# Statemachine_ST7735_R03.net
KiCad netlist of a schematic drawn in EAGLE
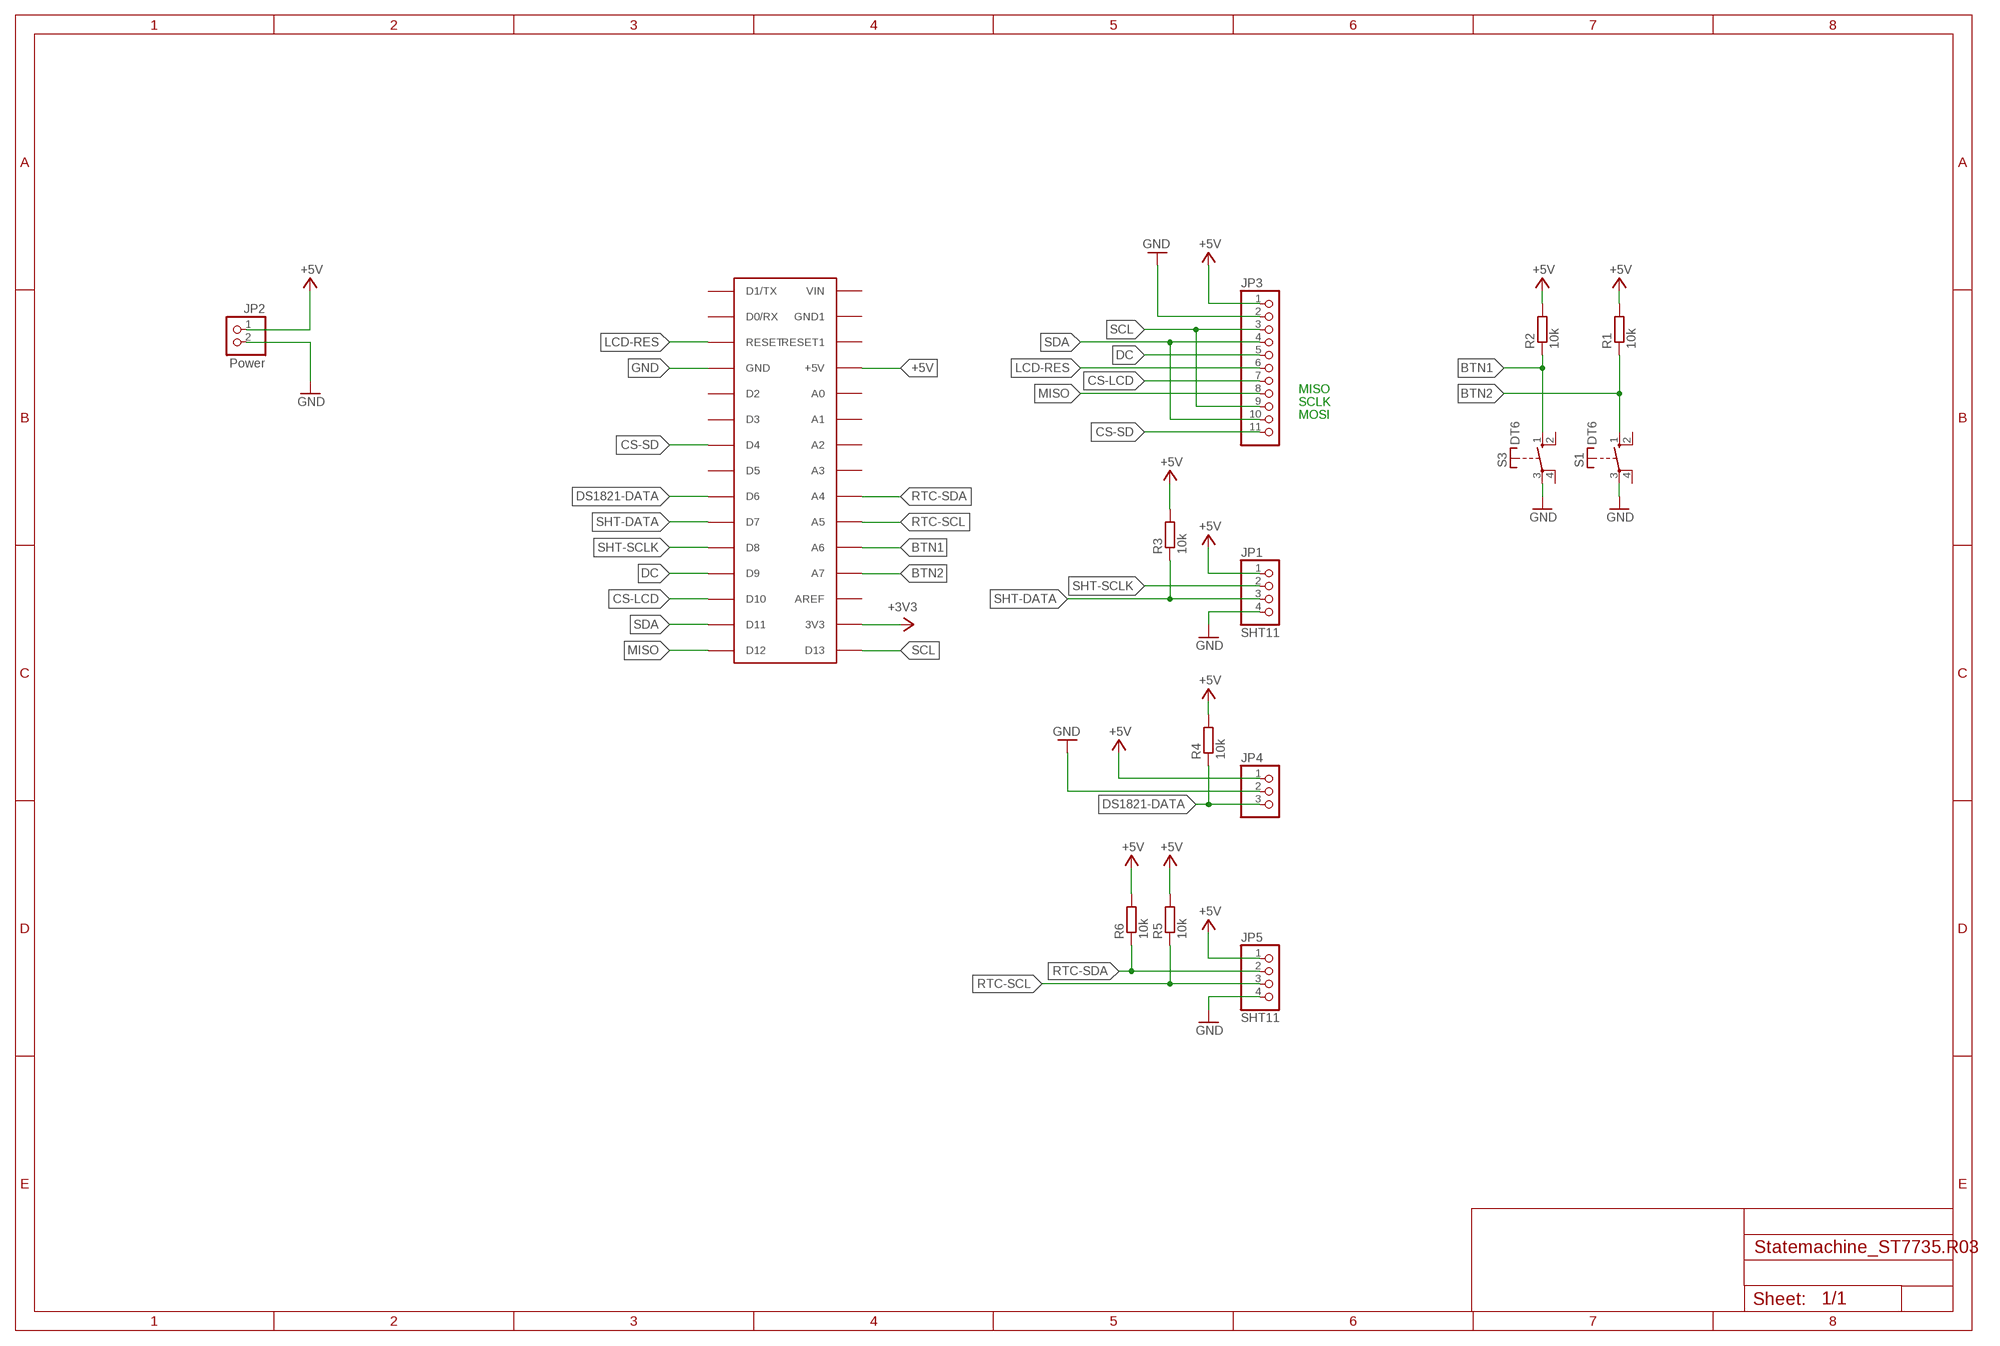
[diagram p0: schematic, sheet 1]

(export (version "E")
  (design (tool "Eeschema 10.0.6"))
  (components
    (comp (ref "JP1")
      (value "SHT11")
      (footprint "eagle-import:1X04")
      (libsource (lib "eagle-import") (part "PINHD-1X4"))
    )
    (comp (ref "JP2")
      (value "Power")
      (footprint "eagle-import:1X02")
      (libsource (lib "eagle-import") (part "PINHD-1X2"))
    )
    (comp (ref "JP3")
      (value "PINHD-1X11")
      (footprint "eagle-import:1X11")
      (libsource (lib "eagle-import") (part "PINHD-1X11"))
    )
    (comp (ref "JP4")
      (value "PINHD-1X3")
      (footprint "eagle-import:1X03")
      (libsource (lib "eagle-import") (part "PINHD-1X3"))
    )
    (comp (ref "JP5")
      (value "SHT11")
      (footprint "eagle-import:1X04")
      (libsource (lib "eagle-import") (part "PINHD-1X4"))
    )
    (comp (ref "NANO")
      (value "ARDUINONANO")
      (footprint "eagle-import:PDIP-32")
      (libsource (lib "eagle-import") (part "ARDUINONANO"))
    )
    (comp (ref "R1")
      (value "10k")
      (footprint "eagle-import:0204_7")
      (libsource (lib "eagle-import") (part "R-EU_0204/7"))
    )
    (comp (ref "R2")
      (value "10k")
      (footprint "eagle-import:0204_7")
      (libsource (lib "eagle-import") (part "R-EU_0204/7"))
    )
    (comp (ref "R3")
      (value "10k")
      (footprint "eagle-import:0204_7")
      (libsource (lib "eagle-import") (part "R-EU_0204/7"))
    )
    (comp (ref "R4")
      (value "10k")
      (footprint "eagle-import:0204_7")
      (libsource (lib "eagle-import") (part "R-EU_0204/7"))
    )
    (comp (ref "R5")
      (value "10k")
      (footprint "eagle-import:0204_7")
      (libsource (lib "eagle-import") (part "R-EU_0204/7"))
    )
    (comp (ref "R6")
      (value "10k")
      (footprint "eagle-import:0204_7")
      (libsource (lib "eagle-import") (part "R-EU_0204/7"))
    )
    (comp (ref "S1")
      (value "DT6")
      (footprint "eagle-import:DT6")
      (libsource (lib "eagle-import") (part "DT6"))
    )
    (comp (ref "S3")
      (value "DT6")
      (footprint "eagle-import:DT6")
      (libsource (lib "eagle-import") (part "DT6"))
    )
  )
  (nets
    (net (code "1") (name "+3V3") (class "Default")
      (node (ref "NANO") (pin "3V3") (pinfunction "3V3_3V3") (pintype "bidirectional"))
    )
    (net (code "2") (name "+5V") (class "Default")
      (node (ref "JP1") (pin "1") (pinfunction "1_1") (pintype "passive"))
      (node (ref "JP2") (pin "1") (pinfunction "1_1") (pintype "passive"))
      (node (ref "JP3") (pin "1") (pinfunction "1_1") (pintype "passive"))
      (node (ref "JP4") (pin "1") (pinfunction "1_1") (pintype "passive"))
      (node (ref "JP5") (pin "1") (pinfunction "1_1") (pintype "passive"))
      (node (ref "NANO") (pin "+5V") (pinfunction "+5V_+5V") (pintype "bidirectional"))
      (node (ref "R1") (pin "2") (pinfunction "2_2") (pintype "passive"))
      (node (ref "R2") (pin "2") (pinfunction "2_2") (pintype "passive"))
      (node (ref "R3") (pin "2") (pinfunction "2_2") (pintype "passive"))
      (node (ref "R4") (pin "2") (pinfunction "2_2") (pintype "passive"))
      (node (ref "R5") (pin "2") (pinfunction "2_2") (pintype "passive"))
      (node (ref "R6") (pin "2") (pinfunction "2_2") (pintype "passive"))
    )
    (net (code "3") (name "BTN1") (class "Default")
      (node (ref "NANO") (pin "A6") (pinfunction "A6_A6") (pintype "bidirectional"))
      (node (ref "R2") (pin "1") (pinfunction "1_1") (pintype "passive"))
      (node (ref "S3") (pin "1") (pinfunction "S_1") (pintype "passive"))
    )
    (net (code "4") (name "BTN2") (class "Default")
      (node (ref "NANO") (pin "A7") (pinfunction "A7_A7") (pintype "bidirectional"))
      (node (ref "R1") (pin "1") (pinfunction "1_1") (pintype "passive"))
      (node (ref "S1") (pin "1") (pinfunction "S_1") (pintype "passive"))
    )
    (net (code "5") (name "CS-LCD") (class "Default")
      (node (ref "JP3") (pin "7") (pinfunction "7_7") (pintype "passive"))
      (node (ref "NANO") (pin "D10") (pinfunction "D10_D10") (pintype "bidirectional"))
    )
    (net (code "6") (name "CS-SD") (class "Default")
      (node (ref "JP3") (pin "11") (pinfunction "11_11") (pintype "passive"))
      (node (ref "NANO") (pin "D4") (pinfunction "D4_D4") (pintype "bidirectional"))
    )
    (net (code "7") (name "DC") (class "Default")
      (node (ref "JP3") (pin "5") (pinfunction "5_5") (pintype "passive"))
      (node (ref "NANO") (pin "D9") (pinfunction "D9_D9") (pintype "bidirectional"))
    )
    (net (code "8") (name "DS1821-DATA") (class "Default")
      (node (ref "JP4") (pin "3") (pinfunction "3_3") (pintype "passive"))
      (node (ref "NANO") (pin "D6") (pinfunction "D6_D6") (pintype "bidirectional"))
      (node (ref "R4") (pin "1") (pinfunction "1_1") (pintype "passive"))
    )
    (net (code "9") (name "GND") (class "Default")
      (node (ref "JP1") (pin "4") (pinfunction "4_4") (pintype "passive"))
      (node (ref "JP2") (pin "2") (pinfunction "2_2") (pintype "passive"))
      (node (ref "JP3") (pin "2") (pinfunction "2_2") (pintype "passive"))
      (node (ref "JP4") (pin "2") (pinfunction "2_2") (pintype "passive"))
      (node (ref "JP5") (pin "4") (pinfunction "4_4") (pintype "passive"))
      (node (ref "NANO") (pin "GND") (pinfunction "GND_GND") (pintype "bidirectional"))
      (node (ref "S1") (pin "3") (pinfunction "P_3") (pintype "passive"))
      (node (ref "S3") (pin "3") (pinfunction "P_3") (pintype "passive"))
    )
    (net (code "10") (name "LCD-RES") (class "Default")
      (node (ref "JP3") (pin "6") (pinfunction "6_6") (pintype "passive"))
      (node (ref "NANO") (pin "RESET") (pinfunction "RESET_RESET") (pintype "bidirectional"))
    )
    (net (code "11") (name "MISO") (class "Default")
      (node (ref "JP3") (pin "8") (pinfunction "8_8") (pintype "passive"))
      (node (ref "NANO") (pin "D12") (pinfunction "D12_D12") (pintype "bidirectional"))
    )
    (net (code "12") (name "RTC-SCL") (class "Default")
      (node (ref "JP5") (pin "3") (pinfunction "3_3") (pintype "passive"))
      (node (ref "NANO") (pin "A5") (pinfunction "A5_A5") (pintype "bidirectional"))
      (node (ref "R5") (pin "1") (pinfunction "1_1") (pintype "passive"))
    )
    (net (code "13") (name "RTC-SDA") (class "Default")
      (node (ref "JP5") (pin "2") (pinfunction "2_2") (pintype "passive"))
      (node (ref "NANO") (pin "A4") (pinfunction "A4_A4") (pintype "bidirectional"))
      (node (ref "R6") (pin "1") (pinfunction "1_1") (pintype "passive"))
    )
    (net (code "14") (name "SCL") (class "Default")
      (node (ref "JP3") (pin "3") (pinfunction "3_3") (pintype "passive"))
      (node (ref "JP3") (pin "9") (pinfunction "9_9") (pintype "passive"))
      (node (ref "NANO") (pin "D13") (pinfunction "D13_D13") (pintype "bidirectional"))
    )
    (net (code "15") (name "SDA") (class "Default")
      (node (ref "JP3") (pin "10") (pinfunction "10_10") (pintype "passive"))
      (node (ref "JP3") (pin "4") (pinfunction "4_4") (pintype "passive"))
      (node (ref "NANO") (pin "D11") (pinfunction "D11_D11") (pintype "bidirectional"))
    )
    (net (code "16") (name "SHT-DATA") (class "Default")
      (node (ref "JP1") (pin "3") (pinfunction "3_3") (pintype "passive"))
      (node (ref "NANO") (pin "D7") (pinfunction "D7_D7") (pintype "bidirectional"))
      (node (ref "R3") (pin "1") (pinfunction "1_1") (pintype "passive"))
    )
    (net (code "17") (name "SHT-SCLK") (class "Default")
      (node (ref "JP1") (pin "2") (pinfunction "2_2") (pintype "passive"))
      (node (ref "NANO") (pin "D8") (pinfunction "D8_D8") (pintype "bidirectional"))
    )
    (net (code "18") (name "unconnected-(NANO-PadA0)") (class "Default")
      (node (ref "NANO") (pin "A0") (pinfunction "A0_A0") (pintype "bidirectional"))
    )
    (net (code "19") (name "unconnected-(NANO-PadA1)") (class "Default")
      (node (ref "NANO") (pin "A1") (pinfunction "A1_A1") (pintype "bidirectional"))
    )
    (net (code "20") (name "unconnected-(NANO-PadA2)") (class "Default")
      (node (ref "NANO") (pin "A2") (pinfunction "A2_A2") (pintype "bidirectional"))
    )
    (net (code "21") (name "unconnected-(NANO-PadA3)") (class "Default")
      (node (ref "NANO") (pin "A3") (pinfunction "A3_A3") (pintype "bidirectional"))
    )
    (net (code "22") (name "unconnected-(NANO-PadAREF)") (class "Default")
      (node (ref "NANO") (pin "AREF") (pinfunction "AREF_AREF") (pintype "bidirectional"))
    )
    (net (code "23") (name "unconnected-(NANO-PadD0{slash}RX)") (class "Default")
      (node (ref "NANO") (pin "D0/RX") (pinfunction "D0/RX_D0/RX") (pintype "bidirectional"))
    )
    (net (code "24") (name "unconnected-(NANO-PadD1{slash}TX)") (class "Default")
      (node (ref "NANO") (pin "D1/TX") (pinfunction "D1/TX_D1/TX") (pintype "bidirectional"))
    )
    (net (code "25") (name "unconnected-(NANO-PadD2)") (class "Default")
      (node (ref "NANO") (pin "D2") (pinfunction "D2_D2") (pintype "bidirectional"))
    )
    (net (code "26") (name "unconnected-(NANO-PadD3)") (class "Default")
      (node (ref "NANO") (pin "D3") (pinfunction "D3_D3") (pintype "bidirectional"))
    )
    (net (code "27") (name "unconnected-(NANO-PadD5)") (class "Default")
      (node (ref "NANO") (pin "D5") (pinfunction "D5_D5") (pintype "bidirectional"))
    )
    (net (code "28") (name "unconnected-(NANO-PadGND1)") (class "Default")
      (node (ref "NANO") (pin "GND1") (pinfunction "GND1_GND1") (pintype "bidirectional"))
    )
    (net (code "29") (name "unconnected-(NANO-PadRESET1)") (class "Default")
      (node (ref "NANO") (pin "RESET1") (pinfunction "RESET1_RESET1") (pintype "bidirectional"))
    )
    (net (code "30") (name "unconnected-(NANO-PadVIN)") (class "Default")
      (node (ref "NANO") (pin "VIN") (pinfunction "VIN_VIN") (pintype "bidirectional"))
    )
    (net (code "31") (name "unconnected-(S1-P-Pad4)") (class "Default")
      (node (ref "S1") (pin "4") (pinfunction "P_4") (pintype "passive"))
    )
    (net (code "32") (name "unconnected-(S1-S-Pad2)") (class "Default")
      (node (ref "S1") (pin "2") (pinfunction "S_2") (pintype "passive"))
    )
    (net (code "33") (name "unconnected-(S3-P-Pad4)") (class "Default")
      (node (ref "S3") (pin "4") (pinfunction "P_4") (pintype "passive"))
    )
    (net (code "34") (name "unconnected-(S3-S-Pad2)") (class "Default")
      (node (ref "S3") (pin "2") (pinfunction "S_2") (pintype "passive"))
    )
  )
)
